# 425AK01A_S02.net
KiCad netlist of a schematic drawn in Altium Designer
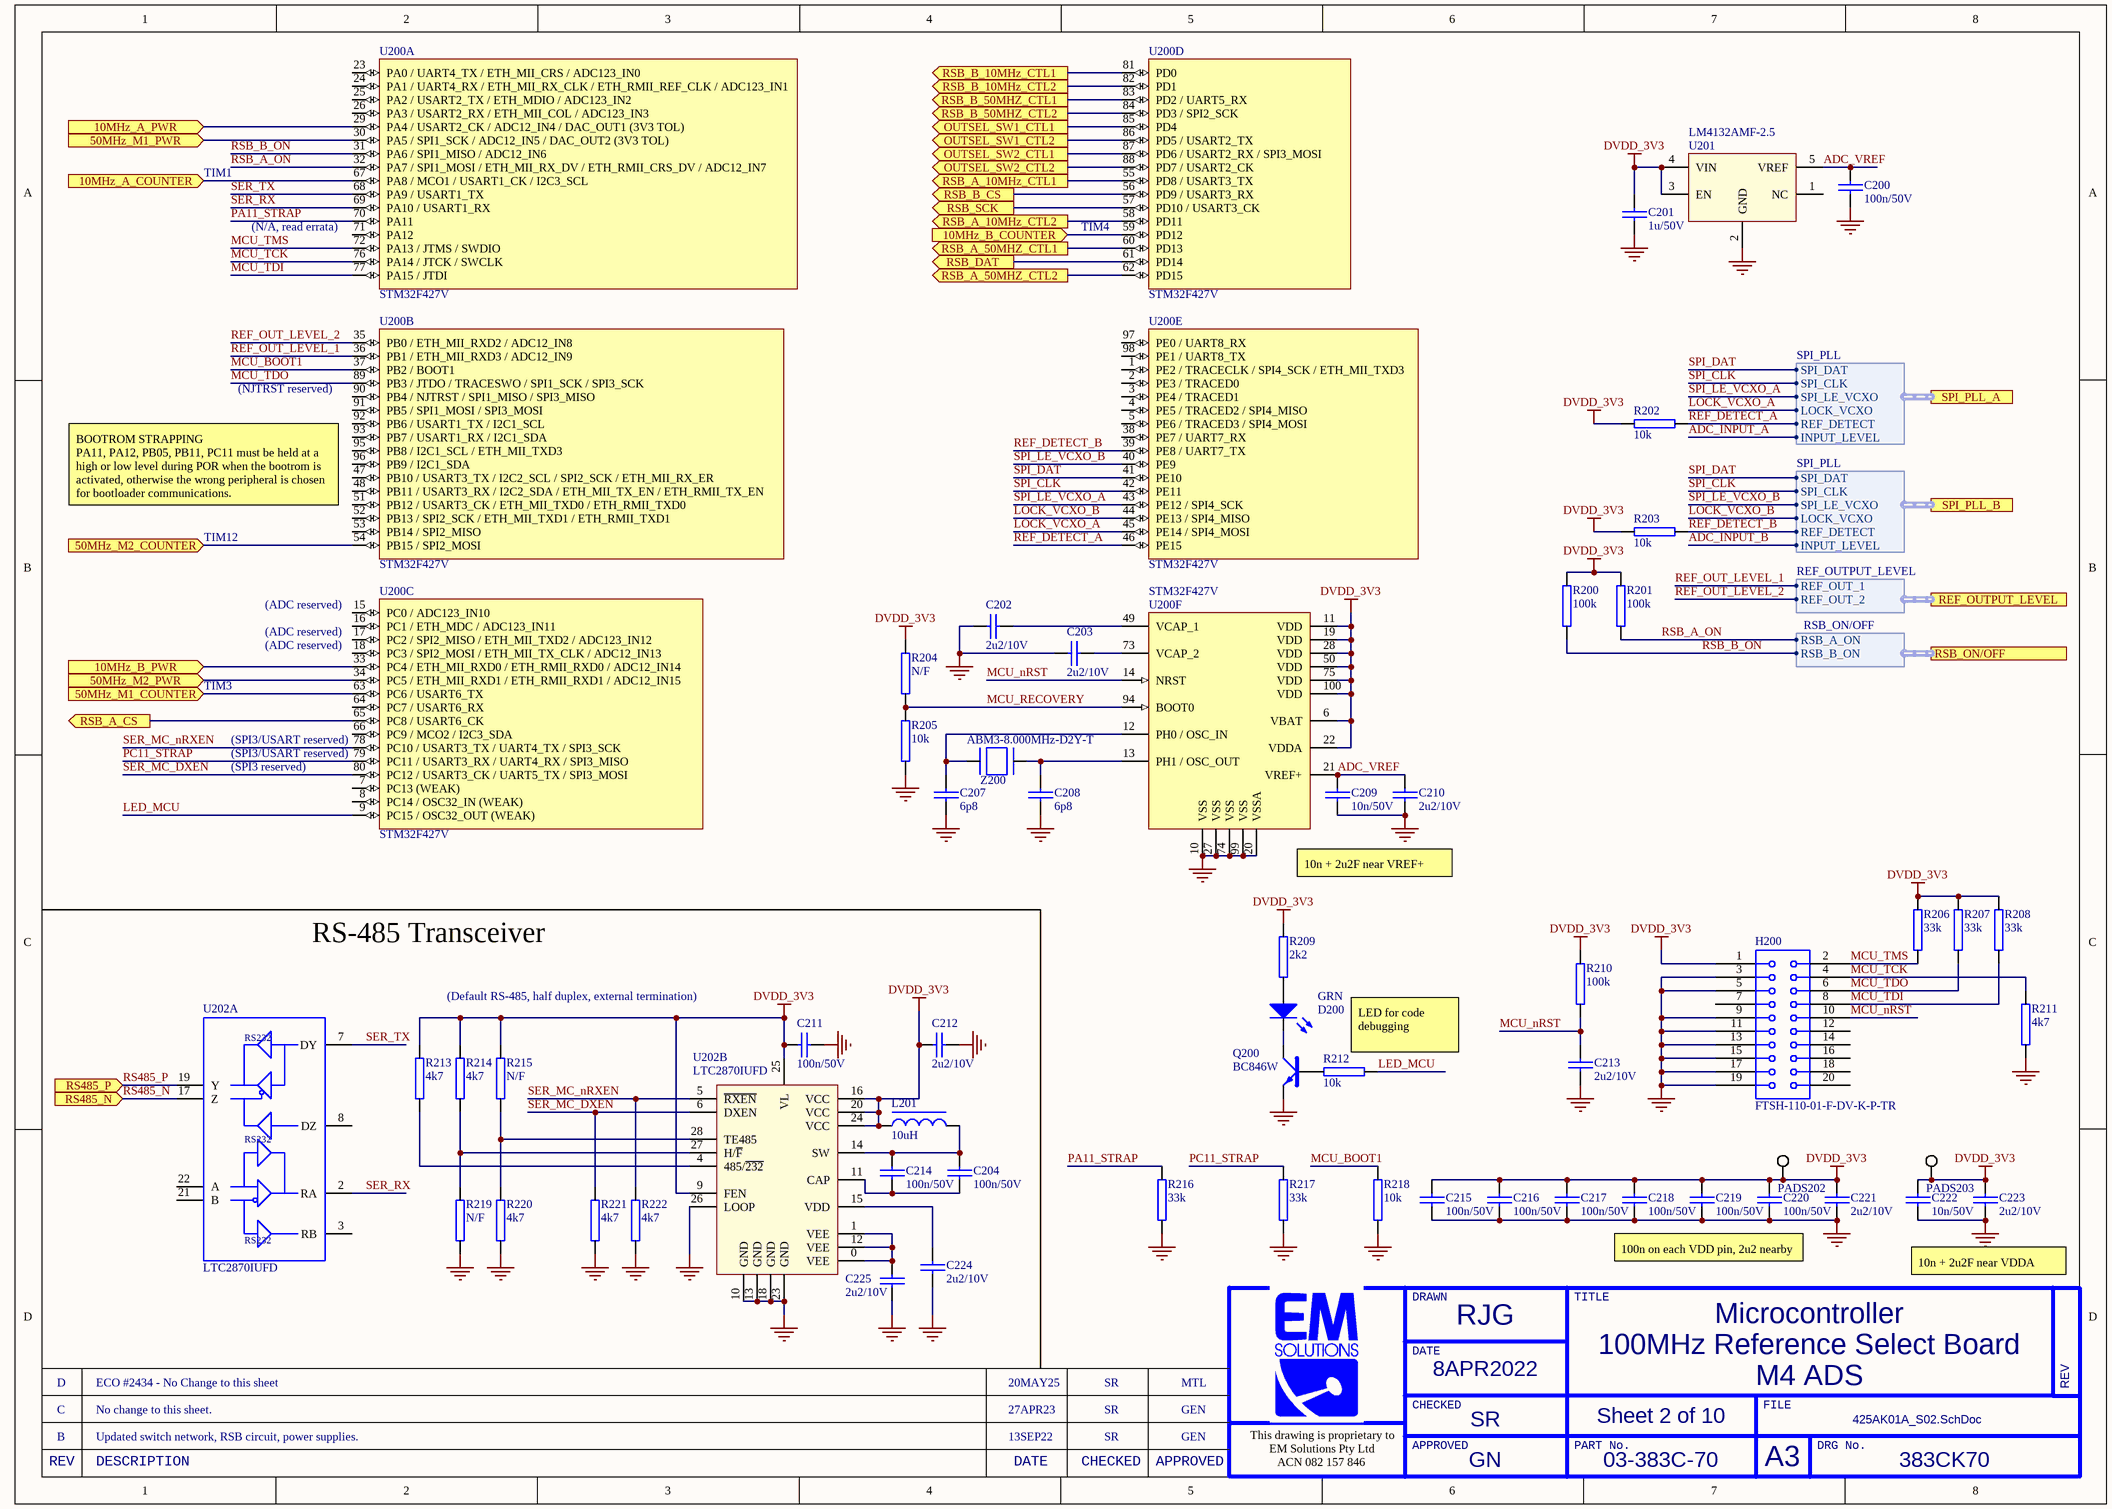
[diagram p0: 425AK01A_S02.SchDoc]

(export (version "E")
  (design (tool "Eeschema 10.0.6"))
  (components
    (comp (ref "C200")
      (value "100n/50V")
      (footprint "0402C")
      (description "Capacitor, 0402, 100n, X7R, 10% 50V, Ceramic")
      (fields (field (name "PART NUMBER") "41-100N-13") (field (name "MANUFACTURER") "MURATA"))
      (libsource (lib "EM DFM Library") (part "CAP"))
    )
    (comp (ref "C201")
      (value "1u/50V")
      (footprint "0603C")
      (description "Capacitor, 0603, 1u X7R 10% 50V Ceramic, NiSn")
      (fields (field (name "PART NUMBER") "41-01U0-06") (field (name "MANUFACTURER") "TAIYOYUDEN"))
      (libsource (lib "EM DFM Library") (part "CAP"))
    )
    (comp (ref "C202")
      (value "2u2/10V")
      (footprint "0603C")
      (description "Capacitor, 0603, 2u2 X7R 10% 10V Ceramic, NiSn")
      (fields (field (name "PART NUMBER") "41-02U2-06") (field (name "MANUFACTURER") "MURATA"))
      (libsource (lib "EM DFM Library") (part "CAP"))
    )
    (comp (ref "C203")
      (value "2u2/10V")
      (footprint "0603C")
      (description "Capacitor, 0603, 2u2 X7R 10% 10V Ceramic, NiSn")
      (fields (field (name "PART NUMBER") "41-02U2-06") (field (name "MANUFACTURER") "MURATA"))
      (libsource (lib "EM DFM Library") (part "CAP"))
    )
    (comp (ref "C204")
      (value "100n/50V")
      (footprint "0402C")
      (description "Capacitor, 0402, 100n, X7R, 10% 50V, Ceramic")
      (fields (field (name "PART NUMBER") "41-100N-13") (field (name "MANUFACTURER") "MURATA"))
      (libsource (lib "EM DFM Library") (part "CAP"))
    )
    (comp (ref "C207")
      (value "6p8")
      (footprint "0402C")
      (description "Capacitor, 0402, 6p8 NPO +/- 0.1p 50V HiQ, NiSn")
      (fields (field (name "PART NUMBER") "41-06P8-05") (field (name "MANUFACTURER") "MURATA"))
      (libsource (lib "EM DFM Library") (part "CAP"))
    )
    (comp (ref "C208")
      (value "6p8")
      (footprint "0402C")
      (description "Capacitor, 0402, 6p8 NPO +/- 0.1p 50V HiQ, NiSn")
      (fields (field (name "PART NUMBER") "41-06P8-05") (field (name "MANUFACTURER") "MURATA"))
      (libsource (lib "EM DFM Library") (part "CAP"))
    )
    (comp (ref "C209")
      (value "10n/50V")
      (footprint "0402C")
      (description "Capacitor, 0402, 10n X7R 10% 50V Ceramic, NiSn")
      (fields (field (name "PART NUMBER") "41-010N-12") (field (name "MANUFACTURER") "MURATA"))
      (libsource (lib "EM DFM Library") (part "CAP"))
    )
    (comp (ref "C210")
      (value "2u2/10V")
      (footprint "0603C")
      (description "Capacitor, 0603, 2u2 X7R 10% 10V Ceramic, NiSn")
      (fields (field (name "PART NUMBER") "41-02U2-06") (field (name "MANUFACTURER") "MURATA"))
      (libsource (lib "EM DFM Library") (part "CAP"))
    )
    (comp (ref "C211")
      (value "100n/50V")
      (footprint "0402C")
      (description "Capacitor, 0402, 100n, X7R, 10% 50V, Ceramic")
      (fields (field (name "PART NUMBER") "41-100N-13") (field (name "MANUFACTURER") "MURATA"))
      (libsource (lib "EM DFM Library") (part "CAP"))
    )
    (comp (ref "C212")
      (value "2u2/10V")
      (footprint "0603C")
      (description "Capacitor, 0603, 2u2 X7R 10% 10V Ceramic, NiSn")
      (fields (field (name "PART NUMBER") "41-02U2-06") (field (name "MANUFACTURER") "MURATA"))
      (libsource (lib "EM DFM Library") (part "CAP"))
    )
    (comp (ref "C213")
      (value "2u2/10V")
      (footprint "0603C")
      (description "Capacitor, 0603, 2u2 X7R 10% 10V Ceramic, NiSn")
      (fields (field (name "PART NUMBER") "41-02U2-06") (field (name "MANUFACTURER") "MURATA"))
      (libsource (lib "EM DFM Library") (part "CAP"))
    )
    (comp (ref "C214")
      (value "100n/50V")
      (footprint "0402C")
      (description "Capacitor, 0402, 100n, X7R, 10% 50V, Ceramic")
      (fields (field (name "PART NUMBER") "41-100N-13") (field (name "MANUFACTURER") "MURATA"))
      (libsource (lib "EM DFM Library") (part "CAP"))
    )
    (comp (ref "C215")
      (value "100n/50V")
      (footprint "0402C")
      (description "Capacitor, 0402, 100n, X7R, 10% 50V, Ceramic")
      (fields (field (name "PART NUMBER") "41-100N-13") (field (name "MANUFACTURER") "MURATA"))
      (libsource (lib "EM DFM Library") (part "CAP"))
    )
    (comp (ref "C216")
      (value "100n/50V")
      (footprint "0402C")
      (description "Capacitor, 0402, 100n, X7R, 10% 50V, Ceramic")
      (fields (field (name "PART NUMBER") "41-100N-13") (field (name "MANUFACTURER") "MURATA"))
      (libsource (lib "EM DFM Library") (part "CAP"))
    )
    (comp (ref "C217")
      (value "100n/50V")
      (footprint "0402C")
      (description "Capacitor, 0402, 100n, X7R, 10% 50V, Ceramic")
      (fields (field (name "PART NUMBER") "41-100N-13") (field (name "MANUFACTURER") "MURATA"))
      (libsource (lib "EM DFM Library") (part "CAP"))
    )
    (comp (ref "C218")
      (value "100n/50V")
      (footprint "0402C")
      (description "Capacitor, 0402, 100n, X7R, 10% 50V, Ceramic")
      (fields (field (name "PART NUMBER") "41-100N-13") (field (name "MANUFACTURER") "MURATA"))
      (libsource (lib "EM DFM Library") (part "CAP"))
    )
    (comp (ref "C219")
      (value "100n/50V")
      (footprint "0402C")
      (description "Capacitor, 0402, 100n, X7R, 10% 50V, Ceramic")
      (fields (field (name "PART NUMBER") "41-100N-13") (field (name "MANUFACTURER") "MURATA"))
      (libsource (lib "EM DFM Library") (part "CAP"))
    )
    (comp (ref "C220")
      (value "100n/50V")
      (footprint "0402C")
      (description "Capacitor, 0402, 100n, X7R, 10% 50V, Ceramic")
      (fields (field (name "PART NUMBER") "41-100N-13") (field (name "MANUFACTURER") "MURATA"))
      (libsource (lib "EM DFM Library") (part "CAP"))
    )
    (comp (ref "C221")
      (value "2u2/10V")
      (footprint "0603C")
      (description "Capacitor, 0603, 2u2 X7R 10% 10V Ceramic, NiSn")
      (fields (field (name "PART NUMBER") "41-02U2-06") (field (name "MANUFACTURER") "MURATA"))
      (libsource (lib "EM DFM Library") (part "CAP"))
    )
    (comp (ref "C222")
      (value "10n/50V")
      (footprint "0402C")
      (description "Capacitor, 0402, 10n X7R 10% 50V Ceramic, NiSn")
      (fields (field (name "PART NUMBER") "41-010N-12") (field (name "MANUFACTURER") "MURATA"))
      (libsource (lib "EM DFM Library") (part "CAP"))
    )
    (comp (ref "C223")
      (value "2u2/10V")
      (footprint "0603C")
      (description "Capacitor, 0603, 2u2 X7R 10% 10V Ceramic, NiSn")
      (fields (field (name "PART NUMBER") "41-02U2-06") (field (name "MANUFACTURER") "MURATA"))
      (libsource (lib "EM DFM Library") (part "CAP"))
    )
    (comp (ref "C224")
      (value "2u2/10V")
      (footprint "0603C")
      (description "Capacitor, 0603, 2u2 X7R 10% 10V Ceramic, NiSn")
      (fields (field (name "PART NUMBER") "41-02U2-06") (field (name "MANUFACTURER") "MURATA"))
      (libsource (lib "EM DFM Library") (part "CAP"))
    )
    (comp (ref "C225")
      (value "2u2/10V")
      (footprint "0603C")
      (description "Capacitor, 0603, 2u2 X7R 10% 10V Ceramic, NiSn")
      (fields (field (name "PART NUMBER") "41-02U2-06") (field (name "MANUFACTURER") "MURATA"))
      (libsource (lib "EM DFM Library") (part "CAP"))
    )
    (comp (ref "D200")
      (value "GRN")
      (footprint "0603 LED")
      (description "LED, Green, 0603, 35mcd @ 20mA")
      (fields (field (name "PART NUMBER") "57-190-01") (field (name "MANUFACTURER") "LIGHTON"))
      (libsource (lib "EM DFM Library") (part "LED"))
    )
    (comp (ref "H200")
      (value "FTSH-110-01-F-DV-K-P-TR")
      (footprint "FTSH-110-01-F-DV-K")
      (description "PCB Header, 10+10way, 1.27mm, Polarised, SMD, Pick and Place")
      (fields (field (name "PART NUMBER") "20-H20-04") (field (name "MANUFACTURER") "SAMTEC"))
      (libsource (lib "EM DFM Library") (part "Header20"))
    )
    (comp (ref "L201")
      (value "10uH")
      (footprint "0805L")
      (description "Inductor, Chip, 10uH 20%, SRF=50MHz, 0805 MLZ series")
      (fields (field (name "PART NUMBER") "46-010U-03") (field (name "MANUFACTURER") "TDK"))
      (libsource (lib "EM DFM Library") (part "IND"))
    )
    (comp (ref "PADS202")
      (value "Pads")
      (footprint "Pads-1x3-V3-0.3/0.6mm")
      (description "Cluster of pads")
      (libsource (lib "Russell") (part "Pads"))
    )
    (comp (ref "PADS203")
      (value "Pads")
      (footprint "Pads-1x3-V3-0.3/0.6mm")
      (description "Cluster of pads")
      (libsource (lib "Russell") (part "Pads"))
    )
    (comp (ref "Q200")
      (value "BC846W")
      (footprint "SOT-323BJT")
      (description "Transistor, NPN Si, GenPur 65V 100mA, SOT-323")
      (fields (field (name "PART NUMBER") "62-BC846-01") (field (name "MANUFACTURER") "TAIWAN SEMI"))
      (libsource (lib "EM DFM Library") (part "NPN"))
    )
    (comp (ref "R200")
      (value "100k")
      (footprint "0402")
      (description "Resistor, 0402, 100k 1% 0.063W")
      (fields (field (name "PART NUMBER") "44-100K-10") (field (name "MANUFACTURER") "PHILIPS"))
      (libsource (lib "EM DFM Library") (part "RES"))
    )
    (comp (ref "R201")
      (value "100k")
      (footprint "0402")
      (description "Resistor, 0402, 100k 1% 0.063W")
      (fields (field (name "PART NUMBER") "44-100K-10") (field (name "MANUFACTURER") "PHILIPS"))
      (libsource (lib "EM DFM Library") (part "RES"))
    )
    (comp (ref "R202")
      (value "10k")
      (footprint "0402")
      (description "Resistor, 0402, 10k 1% 0.063W")
      (fields (field (name "PART NUMBER") "44-010K-10") (field (name "MANUFACTURER") "PHILIPS"))
      (libsource (lib "EM DFM Library") (part "RES"))
    )
    (comp (ref "R203")
      (value "10k")
      (footprint "0402")
      (description "Resistor, 0402, 10k 1% 0.063W")
      (fields (field (name "PART NUMBER") "44-010K-10") (field (name "MANUFACTURER") "PHILIPS"))
      (libsource (lib "EM DFM Library") (part "RES"))
    )
    (comp (ref "R204")
      (value "N/F")
      (footprint "0402")
      (description "Resistor, 0402, SOT, Not Fitted")
      (fields (field (name "PART NUMBER") "44-N/F-10"))
      (libsource (lib "EM DFM Library") (part "RES"))
    )
    (comp (ref "R205")
      (value "10k")
      (footprint "0402")
      (description "Resistor, 0402, 10k 1% 0.063W")
      (fields (field (name "PART NUMBER") "44-010K-10") (field (name "MANUFACTURER") "PHILIPS"))
      (libsource (lib "EM DFM Library") (part "RES"))
    )
    (comp (ref "R206")
      (value "33k")
      (footprint "0402")
      (description "Resistor, 0402, 33k 1% 0.063W")
      (fields (field (name "PART NUMBER") "44-033K-10") (field (name "MANUFACTURER") "PHILIPS"))
      (libsource (lib "EM DFM Library") (part "RES"))
    )
    (comp (ref "R207")
      (value "33k")
      (footprint "0402")
      (description "Resistor, 0402, 33k 1% 0.063W")
      (fields (field (name "PART NUMBER") "44-033K-10") (field (name "MANUFACTURER") "PHILIPS"))
      (libsource (lib "EM DFM Library") (part "RES"))
    )
    (comp (ref "R208")
      (value "33k")
      (footprint "0402")
      (description "Resistor, 0402, 33k 1% 0.063W")
      (fields (field (name "PART NUMBER") "44-033K-10") (field (name "MANUFACTURER") "PHILIPS"))
      (libsource (lib "EM DFM Library") (part "RES"))
    )
    (comp (ref "R209")
      (value "2k2")
      (footprint "0402")
      (description "Resistor, 0402, 2k2 1% 0.063W")
      (fields (field (name "PART NUMBER") "44-02K2-10") (field (name "MANUFACTURER") "PHILIPS"))
      (libsource (lib "EM DFM Library") (part "RES"))
    )
    (comp (ref "R210")
      (value "100k")
      (footprint "0402")
      (description "Resistor, 0402, 100k 1% 0.063W")
      (fields (field (name "PART NUMBER") "44-100K-10") (field (name "MANUFACTURER") "PHILIPS"))
      (libsource (lib "EM DFM Library") (part "RES"))
    )
    (comp (ref "R211")
      (value "4k7")
      (footprint "0402")
      (description "Resistor, 0402, 4k7 1% 0.063W")
      (fields (field (name "PART NUMBER") "44-04K7-10") (field (name "MANUFACTURER") "PHILIPS"))
      (libsource (lib "EM DFM Library") (part "RES"))
    )
    (comp (ref "R212")
      (value "10k")
      (footprint "0402")
      (description "Resistor, 0402, 10k 1% 0.063W")
      (fields (field (name "PART NUMBER") "44-010K-10") (field (name "MANUFACTURER") "PHILIPS"))
      (libsource (lib "EM DFM Library") (part "RES"))
    )
    (comp (ref "R213")
      (value "4k7")
      (footprint "0402")
      (description "Resistor, 0402, 4k7 1% 0.063W")
      (fields (field (name "PART NUMBER") "44-04K7-10") (field (name "MANUFACTURER") "PHILIPS"))
      (libsource (lib "EM DFM Library") (part "RES"))
    )
    (comp (ref "R214")
      (value "4k7")
      (footprint "0402")
      (description "Resistor, 0402, 4k7 1% 0.063W")
      (fields (field (name "PART NUMBER") "44-04K7-10") (field (name "MANUFACTURER") "GENERIC"))
      (libsource (lib "EM DFM Library") (part "RES"))
    )
    (comp (ref "R215")
      (value "N/F")
      (footprint "0402")
      (description "Resistor,0402,SOT,Not Fitted")
      (fields (field (name "PART NUMBER") "44-N/F-10") (field (name "MANUFACTURER") "PHILIPS"))
      (libsource (lib "EM DFM Library") (part "RES"))
    )
    (comp (ref "R216")
      (value "33k")
      (footprint "0402")
      (description "Resistor, 0402, 33k 1% 0.063W")
      (fields (field (name "PART NUMBER") "44-033K-10") (field (name "MANUFACTURER") "PHILIPS"))
      (libsource (lib "EM DFM Library") (part "RES"))
    )
    (comp (ref "R217")
      (value "33k")
      (footprint "0402")
      (description "Resistor, 0402, 33k 1% 0.063W")
      (fields (field (name "PART NUMBER") "44-033K-10") (field (name "MANUFACTURER") "PHILIPS"))
      (libsource (lib "EM DFM Library") (part "RES"))
    )
    (comp (ref "R218")
      (value "10k")
      (footprint "0402")
      (description "Resistor, 0402, 10k 1% 0.063W")
      (fields (field (name "PART NUMBER") "44-010K-10") (field (name "MANUFACTURER") "PHILIPS"))
      (libsource (lib "EM DFM Library") (part "RES"))
    )
    (comp (ref "R219")
      (value "N/F")
      (footprint "0402")
      (description "Resistor,0402,SOT,Not Fitted")
      (fields (field (name "PART NUMBER") "44-N/F-10") (field (name "MANUFACTURER") "PHILIPS"))
      (libsource (lib "EM DFM Library") (part "RES"))
    )
    (comp (ref "R220")
      (value "4k7")
      (footprint "0402")
      (description "Resistor, 0402, 4k7 1% 0.063W")
      (fields (field (name "PART NUMBER") "44-04K7-10") (field (name "MANUFACTURER") "PHILIPS"))
      (libsource (lib "EM DFM Library") (part "RES"))
    )
    (comp (ref "R221")
      (value "4k7")
      (footprint "0402")
      (description "Resistor, 0402, 4k7 1% 0.063W")
      (fields (field (name "PART NUMBER") "44-04K7-10") (field (name "MANUFACTURER") "PHILIPS"))
      (libsource (lib "EM DFM Library") (part "RES"))
    )
    (comp (ref "R222")
      (value "4k7")
      (footprint "0402")
      (description "Resistor, 0402, 4k7 1% 0.063W")
      (fields (field (name "PART NUMBER") "44-04K7-10") (field (name "MANUFACTURER") "PHILIPS"))
      (libsource (lib "EM DFM Library") (part "RES"))
    )
    (comp (ref "U200")
      (value "STM32F427V")
      (footprint "LQFP100")
      (description "Microcontroller, ARM, 32b, 180MHz, 2M Flash, 3V, Ethernet, LQFP100")
      (fields (field (name "PART NUMBER") "51-32F427-01") (field (name "MANUFACTURER") "ST"))
      (libsource (lib "EM DFM Library") (part "STM32F427V"))
    )
    (comp (ref "U201")
      (value "LM4132AMF-2.5")
      (footprint "SOT-23/5")
      (description "Voltage Ref, 2.5V +/-0.05%, 20ppm/degC, -40/+125degC, SOT-23/5")
      (fields (field (name "PART NUMBER") "52-4132-02") (field (name "MANUFACTURER") "TI"))
      (libsource (lib "EM DFM Library") (part "LM4132AMF"))
    )
    (comp (ref "U202")
      (value "LTC2870IUFD")
      (footprint "QFN-28 4x5mm")
      (description "Transceiver RS422/485/RS232, 3V, ESD, -40/+85, QFN28")
      (fields (field (name "PART NUMBER") "53-2870-01") (field (name "MANUFACTURER") "LIN TECH"))
      (libsource (lib "") (part "LTC2870_1"))
    )
    (comp (ref "Z200")
      (value "ABM3-8.000MHz-D2Y-T")
      (footprint "ABM3")
      (description "Cryst, 8.00MHz, +/-30ppm -40/+85, +/-20ppmCal, 18pF, SMD5x3.2")
      (fields (field (name "PART NUMBER") "37-0102"))
      (libsource (lib "EM DFM Library") (part "Crystal"))
    )
  )
  (nets
    (net (code "4") (name "/10MHz_A_COUNTER") (class "Default")
      (node (ref "U200") (pin "67") (pinfunction "PA8_/_MCO1_/_USART1_CK_/_I2C3_SCL_67") (pintype "bidirectional"))
    )
    (net (code "5") (name "/10MHz_A_PWR") (class "Default")
      (node (ref "U200") (pin "29") (pinfunction "PA4_/_USART2_CK_/_ADC12_IN4_/_DAC_OUT1_(3V3_TOL)_29") (pintype "bidirectional"))
    )
    (net (code "6") (name "/10MHz_B_COUNTER") (class "Default")
      (node (ref "U200") (pin "59") (pinfunction "PD12_59") (pintype "bidirectional"))
    )
    (net (code "7") (name "/10MHz_B_PWR") (class "Default")
      (node (ref "U200") (pin "33") (pinfunction "PC4_/_ETH_MII_RXD0_/_ETH_RMII_RXD0_/_ADC12_IN14_33") (pintype "bidirectional"))
    )
    (net (code "8") (name "/50MHz_M1_COUNTER") (class "Default")
      (node (ref "U200") (pin "63") (pinfunction "PC6_/_USART6_TX_63") (pintype "bidirectional"))
    )
    (net (code "9") (name "/50MHz_M1_PWR") (class "Default")
      (node (ref "U200") (pin "30") (pinfunction "PA5_/_SPI1_SCK_/_ADC12_IN5_/_DAC_OUT2_(3V3_TOL)_30") (pintype "bidirectional"))
    )
    (net (code "10") (name "/50MHz_M2_COUNTER") (class "Default")
      (node (ref "U200") (pin "54") (pinfunction "PB15_/_SPI2_MOSI_54") (pintype "bidirectional"))
    )
    (net (code "11") (name "/50MHz_M2_PWR") (class "Default")
      (node (ref "U200") (pin "34") (pinfunction "PC5_/_ETH_MII_RXD1_/_ETH_RMII_RXD1_/_ADC12_IN15_34") (pintype "bidirectional"))
    )
    (net (code "14") (name "/ADC_VREF") (class "Default")
      (node (ref "C200") (pin "2") (pintype "passive"))
      (node (ref "C209") (pin "1") (pintype "passive"))
      (node (ref "C210") (pin "1") (pintype "passive"))
      (node (ref "U200") (pin "21") (pinfunction "VREF+_21") (pintype "power_in"))
      (node (ref "U201") (pin "5") (pinfunction "VREF_5") (pintype "passive"))
    )
    (net (code "15") (name "/LED_MCU") (class "Default")
      (node (ref "R212") (pin "1") (pintype "passive"))
      (node (ref "U200") (pin "9") (pinfunction "PC15_/_OSC32_OUT_(WEAK)_9") (pintype "bidirectional"))
    )
    (net (code "16") (name "/LOCK_VCXO_A") (class "Default")
      (node (ref "U200") (pin "45") (pinfunction "PE14_/_SPI4_MOSI_45") (pintype "bidirectional"))
    )
    (net (code "17") (name "/LOCK_VCXO_B") (class "Default")
      (node (ref "U200") (pin "44") (pinfunction "PE13_/_SPI4_MISO_44") (pintype "bidirectional"))
    )
    (net (code "18") (name "/MCU_BOOT1") (class "Default")
      (node (ref "R218") (pin "2") (pintype "passive"))
      (node (ref "U200") (pin "37") (pinfunction "PB2_/_BOOT1_37") (pintype "bidirectional"))
    )
    (net (code "19") (name "/MCU_RECOVERY") (class "Default")
      (node (ref "R204") (pin "1") (pintype "passive"))
      (node (ref "R205") (pin "2") (pintype "passive"))
      (node (ref "U200") (pin "94") (pinfunction "BOOT0_94") (pintype "input"))
    )
    (net (code "20") (name "/MCU_TCK") (class "Default")
      (node (ref "H200") (pin "4") (pintype "passive"))
      (node (ref "R211") (pin "2") (pintype "passive"))
      (node (ref "U200") (pin "76") (pinfunction "PA14_/_JTCK_/_SWCLK_76") (pintype "bidirectional"))
    )
    (net (code "21") (name "/MCU_TDI") (class "Default")
      (node (ref "H200") (pin "8") (pintype "passive"))
      (node (ref "R208") (pin "1") (pintype "passive"))
      (node (ref "U200") (pin "77") (pinfunction "PA15_/_JTDI_77") (pintype "bidirectional"))
    )
    (net (code "22") (name "/MCU_TDO") (class "Default")
      (node (ref "H200") (pin "6") (pintype "passive"))
      (node (ref "R207") (pin "1") (pintype "passive"))
      (node (ref "U200") (pin "89") (pinfunction "PB3_/_JTDO_/_TRACESWO_/_SPI1_SCK_/_SPI3_SCK_89") (pintype "bidirectional"))
    )
    (net (code "23") (name "/MCU_TMS") (class "Default")
      (node (ref "H200") (pin "2") (pintype "passive"))
      (node (ref "R206") (pin "1") (pintype "passive"))
      (node (ref "U200") (pin "72") (pinfunction "PA13_/_JTMS_/_SWDIO_72") (pintype "bidirectional"))
    )
    (net (code "24") (name "/MCU_nRST") (class "Default")
      (node (ref "C213") (pin "1") (pintype "passive"))
      (node (ref "H200") (pin "10") (pintype "passive"))
      (node (ref "R210") (pin "1") (pintype "passive"))
      (node (ref "U200") (pin "14") (pinfunction "NRST_14") (pintype "input"))
    )
    (net (code "25") (name "/OUTSEL_SW1_CTL1") (class "Default")
      (node (ref "U200") (pin "85") (pinfunction "PD4_85") (pintype "bidirectional"))
    )
    (net (code "26") (name "/OUTSEL_SW1_CTL2") (class "Default")
      (node (ref "U200") (pin "86") (pinfunction "PD5_/_USART2_TX_86") (pintype "bidirectional"))
    )
    (net (code "27") (name "/OUTSEL_SW2_CTL1") (class "Default")
      (node (ref "U200") (pin "87") (pinfunction "PD6_/_USART2_RX_/_SPI3_MOSI_87") (pintype "bidirectional"))
    )
    (net (code "28") (name "/OUTSEL_SW2_CTL2") (class "Default")
      (node (ref "U200") (pin "88") (pinfunction "PD7_/_USART2_CK_88") (pintype "bidirectional"))
    )
    (net (code "29") (name "/PA11_STRAP") (class "Default")
      (node (ref "R216") (pin "2") (pintype "passive"))
      (node (ref "U200") (pin "70") (pinfunction "PA11_70") (pintype "bidirectional"))
    )
    (net (code "30") (name "/PC11_STRAP") (class "Default")
      (node (ref "R217") (pin "2") (pintype "passive"))
      (node (ref "U200") (pin "79") (pinfunction "PC11_/_USART3_RX_/_UART4_RX_/_SPI3_MISO_79") (pintype "bidirectional"))
    )
    (net (code "31") (name "/REF_DETECT_A") (class "Default")
      (node (ref "R202") (pin "1") (pintype "passive"))
      (node (ref "U200") (pin "46") (pinfunction "PE15_46") (pintype "bidirectional"))
    )
    (net (code "32") (name "/REF_DETECT_B") (class "Default")
      (node (ref "R203") (pin "1") (pintype "passive"))
      (node (ref "U200") (pin "39") (pinfunction "PE8_/_UART7_TX_39") (pintype "bidirectional"))
    )
    (net (code "33") (name "/REF_OUT_LEVEL_1") (class "Default")
      (node (ref "U200") (pin "36") (pinfunction "PB1_/_ETH_MII_RXD3_/_ADC12_IN9_36") (pintype "bidirectional"))
    )
    (net (code "34") (name "/REF_OUT_LEVEL_2") (class "Default")
      (node (ref "U200") (pin "35") (pinfunction "PB0_/_ETH_MII_RXD2_/_ADC12_IN8_35") (pintype "bidirectional"))
    )
    (net (code "35") (name "/RS485_N") (class "Default")
      (node (ref "U202") (pin "17") (pinfunction "Z_17") (pintype "passive"))
    )
    (net (code "36") (name "/RS485_P") (class "Default")
      (node (ref "U202") (pin "19") (pinfunction "Y_19") (pintype "passive"))
    )
    (net (code "37") (name "/RSB_A_10MHz_CTL1") (class "Default")
      (node (ref "U200") (pin "55") (pinfunction "PD8_/_USART3_TX_55") (pintype "bidirectional"))
    )
    (net (code "38") (name "/RSB_A_10MHz_CTL2") (class "Default")
      (node (ref "U200") (pin "58") (pinfunction "PD11_58") (pintype "bidirectional"))
    )
    (net (code "39") (name "/RSB_A_50MHZ_CTL1") (class "Default")
      (node (ref "U200") (pin "60") (pinfunction "PD13_60") (pintype "bidirectional"))
    )
    (net (code "40") (name "/RSB_A_50MHZ_CTL2") (class "Default")
      (node (ref "U200") (pin "62") (pinfunction "PD15_62") (pintype "bidirectional"))
    )
    (net (code "41") (name "/RSB_A_CS") (class "Default")
      (node (ref "U200") (pin "65") (pinfunction "PC8_/_USART6_CK_65") (pintype "bidirectional"))
    )
    (net (code "42") (name "/RSB_A_ON") (class "Default")
      (node (ref "R201") (pin "1") (pintype "passive"))
      (node (ref "U200") (pin "32") (pinfunction "PA7_/_SPI1_MOSI_/_ETH_MII_RX_DV_/_ETH_RMII_CRS_DV_/_ADC12_IN7_32") (pintype "bidirectional"))
    )
    (net (code "43") (name "/RSB_B_10MHz_CTL1") (class "Default")
      (node (ref "U200") (pin "81") (pinfunction "PD0_81") (pintype "bidirectional"))
    )
    (net (code "44") (name "/RSB_B_10MHz_CTL2") (class "Default")
      (node (ref "U200") (pin "82") (pinfunction "PD1_82") (pintype "bidirectional"))
    )
    (net (code "45") (name "/RSB_B_50MHZ_CTL1") (class "Default")
      (node (ref "U200") (pin "83") (pinfunction "PD2_/_UART5_RX_83") (pintype "bidirectional"))
    )
    (net (code "46") (name "/RSB_B_50MHZ_CTL2") (class "Default")
      (node (ref "U200") (pin "84") (pinfunction "PD3_/_SPI2_SCK_84") (pintype "bidirectional"))
    )
    (net (code "47") (name "/RSB_B_CS") (class "Default")
      (node (ref "U200") (pin "56") (pinfunction "PD9_/_USART3_RX_56") (pintype "bidirectional"))
    )
    (net (code "48") (name "/RSB_B_ON") (class "Default")
      (node (ref "R200") (pin "1") (pintype "passive"))
      (node (ref "U200") (pin "31") (pinfunction "PA6_/_SPI1_MISO_/_ADC12_IN6_31") (pintype "bidirectional"))
    )
    (net (code "49") (name "/RSB_DAT") (class "Default")
      (node (ref "U200") (pin "61") (pinfunction "PD14_61") (pintype "bidirectional"))
    )
    (net (code "50") (name "/RSB_SCK") (class "Default")
      (node (ref "U200") (pin "57") (pinfunction "PD10_/_USART3_CK_57") (pintype "bidirectional"))
    )
    (net (code "51") (name "/SER_MC_DXEN") (class "Default")
      (node (ref "R221") (pin "1") (pintype "passive"))
      (node (ref "U200") (pin "80") (pinfunction "PC12_/_USART3_CK_/_UART5_TX_/_SPI3_MOSI_80") (pintype "bidirectional"))
      (node (ref "U202") (pin "6") (pinfunction "DXEN_6") (pintype "passive"))
    )
    (net (code "52") (name "/SER_MC_nRXEN") (class "Default")
      (node (ref "R222") (pin "2") (pintype "passive"))
      (node (ref "U200") (pin "78") (pinfunction "PC10_/_USART3_TX_/_UART4_TX_/_SPI3_SCK_78") (pintype "bidirectional"))
      (node (ref "U202") (pin "5") (pinfunction "~{RXEN}_5") (pintype "passive"))
    )
    (net (code "53") (name "/SER_RX") (class "Default")
      (node (ref "U200") (pin "69") (pinfunction "PA10_/_USART1_RX_69") (pintype "bidirectional"))
      (node (ref "U202") (pin "2") (pinfunction "RA_2") (pintype "passive"))
    )
    (net (code "54") (name "/SER_TX") (class "Default")
      (node (ref "U200") (pin "68") (pinfunction "PA9_/_USART1_TX_68") (pintype "bidirectional"))
      (node (ref "U202") (pin "7") (pinfunction "DY_7") (pintype "passive"))
    )
    (net (code "55") (name "/SPI_CLK") (class "Default")
      (node (ref "U200") (pin "42") (pinfunction "PE11_42") (pintype "bidirectional"))
    )
    (net (code "56") (name "/SPI_DAT") (class "Default")
      (node (ref "U200") (pin "41") (pinfunction "PE10_41") (pintype "bidirectional"))
    )
    (net (code "57") (name "/SPI_LE_VCXO_A") (class "Default")
      (node (ref "U200") (pin "43") (pinfunction "PE12_/_SPI4_SCK_43") (pintype "bidirectional"))
    )
    (net (code "58") (name "/SPI_LE_VCXO_B") (class "Default")
      (node (ref "U200") (pin "40") (pinfunction "PE9_40") (pintype "bidirectional"))
    )
    (net (code "62") (name "DVDD_3V3") (class "Default")
      (node (ref "C201") (pin "1") (pintype "passive"))
      (node (ref "C211") (pin "1") (pintype "passive"))
      (node (ref "C212") (pin "1") (pintype "passive"))
      (node (ref "C215") (pin "1") (pintype "passive"))
      (node (ref "C216") (pin "1") (pintype "passive"))
      (node (ref "C217") (pin "1") (pintype "passive"))
      (node (ref "C218") (pin "1") (pintype "passive"))
      (node (ref "C219") (pin "1") (pintype "passive"))
      (node (ref "C220") (pin "1") (pintype "passive"))
      (node (ref "C221") (pin "1") (pintype "passive"))
      (node (ref "C222") (pin "1") (pintype "passive"))
      (node (ref "C223") (pin "1") (pintype "passive"))
      (node (ref "H200") (pin "1") (pintype "passive"))
      (node (ref "L201") (pin "1") (pinfunction "1_1") (pintype "passive"))
      (node (ref "PADS202") (pin "1") (pinfunction "1_1") (pintype "passive"))
      (node (ref "PADS203") (pin "1") (pinfunction "1_1") (pintype "passive"))
      (node (ref "R200") (pin "2") (pintype "passive"))
      (node (ref "R201") (pin "2") (pintype "passive"))
      (node (ref "R202") (pin "2") (pintype "passive"))
      (node (ref "R203") (pin "2") (pintype "passive"))
      (node (ref "R204") (pin "2") (pintype "passive"))
      (node (ref "R206") (pin "2") (pintype "passive"))
      (node (ref "R207") (pin "2") (pintype "passive"))
      (node (ref "R208") (pin "2") (pintype "passive"))
      (node (ref "R209") (pin "2") (pintype "passive"))
      (node (ref "R210") (pin "2") (pintype "passive"))
      (node (ref "R213") (pin "2") (pintype "passive"))
      (node (ref "R214") (pin "2") (pintype "passive"))
      (node (ref "R215") (pin "2") (pintype "passive"))
      (node (ref "U200") (pin "100") (pinfunction "VDD_100") (pintype "power_in"))
      (node (ref "U200") (pin "11") (pinfunction "VDD_11") (pintype "power_in"))
      (node (ref "U200") (pin "19") (pinfunction "VDD_19") (pintype "power_in"))
      (node (ref "U200") (pin "22") (pinfunction "VDDA_22") (pintype "power_in"))
      (node (ref "U200") (pin "28") (pinfunction "VDD_28") (pintype "power_in"))
      (node (ref "U200") (pin "50") (pinfunction "VDD_50") (pintype "power_in"))
      (node (ref "U200") (pin "6") (pinfunction "VBAT_6") (pintype "power_in"))
      (node (ref "U200") (pin "75") (pinfunction "VDD_75") (pintype "power_in"))
      (node (ref "U201") (pin "3") (pinfunction "EN_3") (pintype "power_in"))
      (node (ref "U201") (pin "4") (pinfunction "VIN_4") (pintype "power_in"))
      (node (ref "U202") (pin "16") (pinfunction "VCC_16") (pintype "passive"))
      (node (ref "U202") (pin "20") (pinfunction "VCC_20") (pintype "passive"))
      (node (ref "U202") (pin "24") (pinfunction "VCC_24") (pintype "passive"))
      (node (ref "U202") (pin "25") (pinfunction "VL_25") (pintype "power_in"))
      (node (ref "U202") (pin "9") (pinfunction "FEN_9") (pintype "passive"))
    )
    (net (code "63") (name "GND") (class "Default")
      (node (ref "C200") (pin "1") (pintype "passive"))
      (node (ref "C201") (pin "2") (pintype "passive"))
      (node (ref "C202") (pin "1") (pintype "passive"))
      (node (ref "C203") (pin "2") (pintype "passive"))
      (node (ref "C207") (pin "2") (pintype "passive"))
      (node (ref "C208") (pin "2") (pintype "passive"))
      (node (ref "C209") (pin "2") (pintype "passive"))
      (node (ref "C210") (pin "2") (pintype "passive"))
      (node (ref "C211") (pin "2") (pintype "passive"))
      (node (ref "C212") (pin "2") (pintype "passive"))
      (node (ref "C213") (pin "2") (pintype "passive"))
      (node (ref "C215") (pin "2") (pintype "passive"))
      (node (ref "C216") (pin "2") (pintype "passive"))
      (node (ref "C217") (pin "2") (pintype "passive"))
      (node (ref "C218") (pin "2") (pintype "passive"))
      (node (ref "C219") (pin "2") (pintype "passive"))
      (node (ref "C220") (pin "2") (pintype "passive"))
      (node (ref "C221") (pin "2") (pintype "passive"))
      (node (ref "C222") (pin "2") (pintype "passive"))
      (node (ref "C223") (pin "2") (pintype "passive"))
      (node (ref "C224") (pin "2") (pintype "passive"))
      (node (ref "C225") (pin "2") (pintype "passive"))
      (node (ref "H200") (pin "11") (pintype "passive"))
      (node (ref "H200") (pin "13") (pintype "passive"))
      (node (ref "H200") (pin "15") (pintype "passive"))
      (node (ref "H200") (pin "17") (pintype "passive"))
      (node (ref "H200") (pin "19") (pintype "passive"))
      (node (ref "H200") (pin "3") (pintype "passive"))
      (node (ref "H200") (pin "5") (pintype "passive"))
      (node (ref "H200") (pin "9") (pintype "passive"))
      (node (ref "Q200") (pin "E") (pinfunction "E_E") (pintype "passive"))
      (node (ref "R205") (pin "1") (pintype "passive"))
      (node (ref "R211") (pin "1") (pintype "passive"))
      (node (ref "R216") (pin "1") (pintype "passive"))
      (node (ref "R217") (pin "1") (pintype "passive"))
      (node (ref "R218") (pin "1") (pintype "passive"))
      (node (ref "R219") (pin "1") (pintype "passive"))
      (node (ref "R220") (pin "1") (pintype "passive"))
      (node (ref "R221") (pin "2") (pintype "passive"))
      (node (ref "R222") (pin "1") (pintype "passive"))
      (node (ref "U200") (pin "10") (pinfunction "VSS_10") (pintype "power_in"))
      (node (ref "U200") (pin "20") (pinfunction "VSSA_20") (pintype "power_in"))
      (node (ref "U200") (pin "27") (pinfunction "VSS_27") (pintype "power_in"))
      (node (ref "U200") (pin "74") (pinfunction "VSS_74") (pintype "power_in"))
      (node (ref "U200") (pin "99") (pinfunction "VSS_99") (pintype "power_in"))
      (node (ref "U201") (pin "2") (pinfunction "GND_2") (pintype "power_in"))
      (node (ref "U202") (pin "10") (pinfunction "GND_10") (pintype "power_in"))
      (node (ref "U202") (pin "13") (pinfunction "GND_13") (pintype "power_in"))
      (node (ref "U202") (pin "18") (pinfunction "GND_18") (pintype "power_in"))
      (node (ref "U202") (pin "23") (pinfunction "GND_23") (pintype "power_in"))
      (node (ref "U202") (pin "26") (pinfunction "LOOP_26") (pintype "passive"))
    )
    (net (code "64") (name "Net-(C225-Pad1)") (class "Default")
      (node (ref "C225") (pin "1") (pintype "passive"))
      (node (ref "U202") (pin "0") (pinfunction "VEE_0") (pintype "passive"))
      (node (ref "U202") (pin "1") (pinfunction "VEE_1") (pintype "passive"))
      (node (ref "U202") (pin "12") (pinfunction "VEE_12") (pintype "passive"))
    )
    (net (code "65") (name "Net-(D200-PadA)") (class "Default")
      (node (ref "D200") (pin "A") (pinfunction "A_A") (pintype "passive"))
      (node (ref "R209") (pin "1") (pintype "passive"))
    )
    (net (code "66") (name "Net-(D200-PadK)") (class "Default")
      (node (ref "D200") (pin "K") (pinfunction "K_K") (pintype "passive"))
      (node (ref "Q200") (pin "C") (pinfunction "C_C") (pintype "passive"))
    )
    (net (code "67") (name "Net-(Q200-PadB)") (class "Default")
      (node (ref "Q200") (pin "B") (pinfunction "B_B") (pintype "passive"))
      (node (ref "R212") (pin "2") (pintype "passive"))
    )
    (net (code "68") (name "Net-(U200F-PH0_{slash}_OSC_IN)") (class "Default")
      (node (ref "C207") (pin "1") (pintype "passive"))
      (node (ref "U200") (pin "12") (pinfunction "PH0_/_OSC_IN_12") (pintype "passive"))
      (node (ref "Z200") (pin "1") (pinfunction "1_1") (pintype "passive"))
    )
    (net (code "69") (name "Net-(U200F-PH1_{slash}_OSC_OUT)") (class "Default")
      (node (ref "C208") (pin "1") (pintype "passive"))
      (node (ref "U200") (pin "13") (pinfunction "PH1_/_OSC_OUT_13") (pintype "passive"))
      (node (ref "Z200") (pin "2") (pinfunction "2_2") (pintype "passive"))
    )
    (net (code "70") (name "Net-(U200F-VCAP_1)") (class "Default")
      (node (ref "C202") (pin "2") (pintype "passive"))
      (node (ref "U200") (pin "49") (pinfunction "VCAP_1_49") (pintype "passive"))
    )
    (net (code "71") (name "Net-(U200F-VCAP_2)") (class "Default")
      (node (ref "C203") (pin "1") (pintype "passive"))
      (node (ref "U200") (pin "73") (pinfunction "VCAP_2_73") (pintype "passive"))
    )
    (net (code "72") (name "Net-(U202B-485{slash}~{232})") (class "Default")
      (node (ref "R213") (pin "1") (pintype "passive"))
      (node (ref "U202") (pin "4") (pinfunction "485/~{232}_4") (pintype "passive"))
    )
    (net (code "73") (name "Net-(U202B-CAP)") (class "Default")
      (node (ref "C204") (pin "1") (pintype "passive"))
      (node (ref "C214") (pin "1") (pintype "passive"))
      (node (ref "U202") (pin "11") (pinfunction "CAP_11") (pintype "passive"))
    )
    (net (code "74") (name "Net-(U202B-H{slash}~{F})") (class "Default")
      (node (ref "R214") (pin "1") (pintype "passive"))
      (node (ref "R219") (pin "2") (pintype "passive"))
      (node (ref "U202") (pin "27") (pinfunction "H/~{F}_27") (pintype "passive"))
    )
    (net (code "75") (name "Net-(U202B-SW)") (class "Default")
      (node (ref "C204") (pin "2") (pintype "passive"))
      (node (ref "C214") (pin "2") (pintype "passive"))
      (node (ref "L201") (pin "2") (pinfunction "2_2") (pintype "passive"))
      (node (ref "U202") (pin "14") (pinfunction "SW_14") (pintype "passive"))
    )
    (net (code "76") (name "Net-(U202B-TE485)") (class "Default")
      (node (ref "R215") (pin "1") (pintype "passive"))
      (node (ref "R220") (pin "2") (pintype "passive"))
      (node (ref "U202") (pin "28") (pinfunction "TE485_28") (pintype "passive"))
    )
    (net (code "77") (name "Net-(U202B-VDD)") (class "Default")
      (node (ref "C224") (pin "1") (pintype "passive"))
      (node (ref "U202") (pin "15") (pinfunction "VDD_15") (pintype "passive"))
    )
    (net (code "78") (name "unconnected-(H200-Pad7)") (class "Default")
      (node (ref "H200") (pin "7") (pintype "passive"))
    )
    (net (code "79") (name "unconnected-(H200-Pad12)") (class "Default")
      (node (ref "H200") (pin "12") (pintype "passive"))
    )
    (net (code "80") (name "unconnected-(H200-Pad14)") (class "Default")
      (node (ref "H200") (pin "14") (pintype "passive"))
    )
    (net (code "81") (name "unconnected-(H200-Pad16)") (class "Default")
      (node (ref "H200") (pin "16") (pintype "passive"))
    )
    (net (code "82") (name "unconnected-(H200-Pad18)") (class "Default")
      (node (ref "H200") (pin "18") (pintype "passive"))
    )
    (net (code "83") (name "unconnected-(H200-Pad20)") (class "Default")
      (node (ref "H200") (pin "20") (pintype "passive"))
    )
    (net (code "84") (name "unconnected-(U200A-PA0_{slash}_UART4_TX_{slash}_ETH_MII_CRS_{slash}_ADC123_IN0-Pad23)") (class "Default")
      (node (ref "U200") (pin "23") (pinfunction "PA0_/_UART4_TX_/_ETH_MII_CRS_/_ADC123_IN0_23") (pintype "bidirectional"))
    )
    (net (code "85") (name "unconnected-(U200A-PA1_{slash}_UART4_RX_{slash}_ETH_MII_RX_CLK_{slash}_ETH_RMII_REF_CLK_{slash}_ADC123_IN1-Pad24)") (class "Default")
      (node (ref "U200") (pin "24") (pinfunction "PA1_/_UART4_RX_/_ETH_MII_RX_CLK_/_ETH_RMII_REF_CLK_/_ADC123_IN1_24") (pintype "bidirectional"))
    )
    (net (code "86") (name "unconnected-(U200A-PA2_{slash}_USART2_TX_{slash}_ETH_MDIO_{slash}_ADC123_IN2-Pad25)") (class "Default")
      (node (ref "U200") (pin "25") (pinfunction "PA2_/_USART2_TX_/_ETH_MDIO_/_ADC123_IN2_25") (pintype "bidirectional"))
    )
    (net (code "87") (name "unconnected-(U200A-PA3_{slash}_USART2_RX_{slash}_ETH_MII_COL_{slash}_ADC123_IN3-Pad26)") (class "Default")
      (node (ref "U200") (pin "26") (pinfunction "PA3_/_USART2_RX_/_ETH_MII_COL_/_ADC123_IN3_26") (pintype "bidirectional"))
    )
    (net (code "88") (name "unconnected-(U200A-PA12-Pad71)") (class "Default")
      (node (ref "U200") (pin "71") (pinfunction "PA12_71") (pintype "bidirectional"))
    )
    (net (code "89") (name "unconnected-(U200B-PB4_{slash}_NJTRST_{slash}_SPI1_MISO_{slash}_SPI3_MISO-Pad90)") (class "Default")
      (node (ref "U200") (pin "90") (pinfunction "PB4_/_NJTRST_/_SPI1_MISO_/_SPI3_MISO_90") (pintype "bidirectional"))
    )
    (net (code "90") (name "unconnected-(U200B-PB5_{slash}_SPI1_MOSI_{slash}_SPI3_MOSI-Pad91)") (class "Default")
      (node (ref "U200") (pin "91") (pinfunction "PB5_/_SPI1_MOSI_/_SPI3_MOSI_91") (pintype "bidirectional"))
    )
    (net (code "91") (name "unconnected-(U200B-PB6_{slash}_USART1_TX_{slash}_I2C1_SCL-Pad92)") (class "Default")
      (node (ref "U200") (pin "92") (pinfunction "PB6_/_USART1_TX_/_I2C1_SCL_92") (pintype "bidirectional"))
    )
    (net (code "92") (name "unconnected-(U200B-PB7_{slash}_USART1_RX_{slash}_I2C1_SDA-Pad93)") (class "Default")
      (node (ref "U200") (pin "93") (pinfunction "PB7_/_USART1_RX_/_I2C1_SDA_93") (pintype "bidirectional"))
    )
    (net (code "93") (name "unconnected-(U200B-PB8_{slash}_I2C1_SCL_{slash}_ETH_MII_TXD3-Pad95)") (class "Default")
      (node (ref "U200") (pin "95") (pinfunction "PB8_/_I2C1_SCL_/_ETH_MII_TXD3_95") (pintype "bidirectional"))
    )
    (net (code "94") (name "unconnected-(U200B-PB9_{slash}_I2C1_SDA-Pad96)") (class "Default")
      (node (ref "U200") (pin "96") (pinfunction "PB9_/_I2C1_SDA_96") (pintype "bidirectional"))
    )
    (net (code "95") (name "unconnected-(U200B-PB10_{slash}_USART3_TX_{slash}_I2C2_SCL_{slash}_SPI2_SCK_{slash}_ETH_MII_RX_ER-Pad47)") (class "Default")
      (node (ref "U200") (pin "47") (pinfunction "PB10_/_USART3_TX_/_I2C2_SCL_/_SPI2_SCK_/_ETH_MII_RX_ER_47") (pintype "bidirectional"))
    )
    (net (code "96") (name "unconnected-(U200B-PB11_{slash}_USART3_RX_{slash}_I2C2_SDA_{slash}_ETH_MII_TX_EN_{slash}_ETH_RMII_TX_EN-Pad48)") (class "Default")
      (node (ref "U200") (pin "48") (pinfunction "PB11_/_USART3_RX_/_I2C2_SDA_/_ETH_MII_TX_EN_/_ETH_RMII_TX_EN_48") (pintype "bidirectional"))
    )
    (net (code "97") (name "unconnected-(U200B-PB12_{slash}_USART3_CK_{slash}_ETH_MII_TXD0_{slash}_ETH_RMII_TXD0-Pad51)") (class "Default")
      (node (ref "U200") (pin "51") (pinfunction "PB12_/_USART3_CK_/_ETH_MII_TXD0_/_ETH_RMII_TXD0_51") (pintype "bidirectional"))
    )
    (net (code "98") (name "unconnected-(U200B-PB13_{slash}_SPI2_SCK_{slash}_ETH_MII_TXD1_{slash}_ETH_RMII_TXD1-Pad52)") (class "Default")
      (node (ref "U200") (pin "52") (pinfunction "PB13_/_SPI2_SCK_/_ETH_MII_TXD1_/_ETH_RMII_TXD1_52") (pintype "bidirectional"))
    )
    (net (code "99") (name "unconnected-(U200B-PB14_{slash}_SPI2_MISO-Pad53)") (class "Default")
      (node (ref "U200") (pin "53") (pinfunction "PB14_/_SPI2_MISO_53") (pintype "bidirectional"))
    )
    (net (code "100") (name "unconnected-(U200C-PC0_{slash}_ADC123_IN10-Pad15)") (class "Default")
      (node (ref "U200") (pin "15") (pinfunction "PC0_/_ADC123_IN10_15") (pintype "bidirectional"))
    )
    (net (code "101") (name "unconnected-(U200C-PC1_{slash}_ETH_MDC_{slash}_ADC123_IN11-Pad16)") (class "Default")
      (node (ref "U200") (pin "16") (pinfunction "PC1_/_ETH_MDC_/_ADC123_IN11_16") (pintype "bidirectional"))
    )
    (net (code "102") (name "unconnected-(U200C-PC2_{slash}_SPI2_MISO_{slash}_ETH_MII_TXD2_{slash}_ADC123_IN12-Pad17)") (class "Default")
      (node (ref "U200") (pin "17") (pinfunction "PC2_/_SPI2_MISO_/_ETH_MII_TXD2_/_ADC123_IN12_17") (pintype "bidirectional"))
    )
    (net (code "103") (name "unconnected-(U200C-PC3_{slash}_SPI2_MOSI_{slash}_ETH_MII_TX_CLK_{slash}_ADC12_IN13-Pad18)") (class "Default")
      (node (ref "U200") (pin "18") (pinfunction "PC3_/_SPI2_MOSI_/_ETH_MII_TX_CLK_/_ADC12_IN13_18") (pintype "bidirectional"))
    )
    (net (code "104") (name "unconnected-(U200C-PC7_{slash}_USART6_RX-Pad64)") (class "Default")
      (node (ref "U200") (pin "64") (pinfunction "PC7_/_USART6_RX_64") (pintype "bidirectional"))
    )
    (net (code "105") (name "unconnected-(U200C-PC9_{slash}_MCO2_{slash}_I2C3_SDA-Pad66)") (class "Default")
      (node (ref "U200") (pin "66") (pinfunction "PC9_/_MCO2_/_I2C3_SDA_66") (pintype "bidirectional"))
    )
    (net (code "106") (name "unconnected-(U200C-PC13_(WEAK)-Pad7)") (class "Default")
      (node (ref "U200") (pin "7") (pinfunction "PC13_(WEAK)_7") (pintype "bidirectional"))
    )
    (net (code "107") (name "unconnected-(U200C-PC14_{slash}_OSC32_IN_(WEAK)-Pad8)") (class "Default")
      (node (ref "U200") (pin "8") (pinfunction "PC14_/_OSC32_IN_(WEAK)_8") (pintype "bidirectional"))
    )
    (net (code "108") (name "unconnected-(U200E-PE0_{slash}_UART8_RX-Pad97)") (class "Default")
      (node (ref "U200") (pin "97") (pinfunction "PE0_/_UART8_RX_97") (pintype "bidirectional"))
    )
    (net (code "109") (name "unconnected-(U200E-PE1_{slash}_UART8_TX-Pad98)") (class "Default")
      (node (ref "U200") (pin "98") (pinfunction "PE1_/_UART8_TX_98") (pintype "bidirectional"))
    )
    (net (code "110") (name "unconnected-(U200E-PE2_{slash}_TRACECLK_{slash}_SPI4_SCK_{slash}_ETH_MII_TXD3-Pad1)") (class "Default")
      (node (ref "U200") (pin "1") (pinfunction "PE2_/_TRACECLK_/_SPI4_SCK_/_ETH_MII_TXD3_1") (pintype "bidirectional"))
    )
    (net (code "111") (name "unconnected-(U200E-PE3_{slash}_TRACED0-Pad2)") (class "Default")
      (node (ref "U200") (pin "2") (pinfunction "PE3_/_TRACED0_2") (pintype "bidirectional"))
    )
    (net (code "112") (name "unconnected-(U200E-PE4_{slash}_TRACED1-Pad3)") (class "Default")
      (node (ref "U200") (pin "3") (pinfunction "PE4_/_TRACED1_3") (pintype "bidirectional"))
    )
    (net (code "113") (name "unconnected-(U200E-PE5_{slash}_TRACED2_{slash}_SPI4_MISO-Pad4)") (class "Default")
      (node (ref "U200") (pin "4") (pinfunction "PE5_/_TRACED2_/_SPI4_MISO_4") (pintype "bidirectional"))
    )
    (net (code "114") (name "unconnected-(U200E-PE6_{slash}_TRACED3_{slash}_SPI4_MOSI-Pad5)") (class "Default")
      (node (ref "U200") (pin "5") (pinfunction "PE6_/_TRACED3_/_SPI4_MOSI_5") (pintype "bidirectional"))
    )
    (net (code "115") (name "unconnected-(U200E-PE7_{slash}_UART7_RX-Pad38)") (class "Default")
      (node (ref "U200") (pin "38") (pinfunction "PE7_/_UART7_RX_38") (pintype "bidirectional"))
    )
    (net (code "116") (name "unconnected-(U201-NC-Pad1)") (class "Default")
      (node (ref "U201") (pin "1") (pinfunction "NC_1") (pintype "passive"))
    )
    (net (code "117") (name "unconnected-(U202A-A-Pad22)") (class "Default")
      (node (ref "U202") (pin "22") (pinfunction "A_22") (pintype "passive"))
    )
    (net (code "118") (name "unconnected-(U202A-B-Pad21)") (class "Default")
      (node (ref "U202") (pin "21") (pinfunction "B_21") (pintype "passive"))
    )
    (net (code "119") (name "unconnected-(U202A-DZ-Pad8)") (class "Default")
      (node (ref "U202") (pin "8") (pinfunction "DZ_8") (pintype "passive"))
    )
    (net (code "120") (name "unconnected-(U202A-RB-Pad3)") (class "Default")
      (node (ref "U202") (pin "3") (pinfunction "RB_3") (pintype "passive"))
    )
  )
)
